# nonregulation-level-shifter-mk-2_1.net
KiCad netlist of a schematic drawn in EAGLE
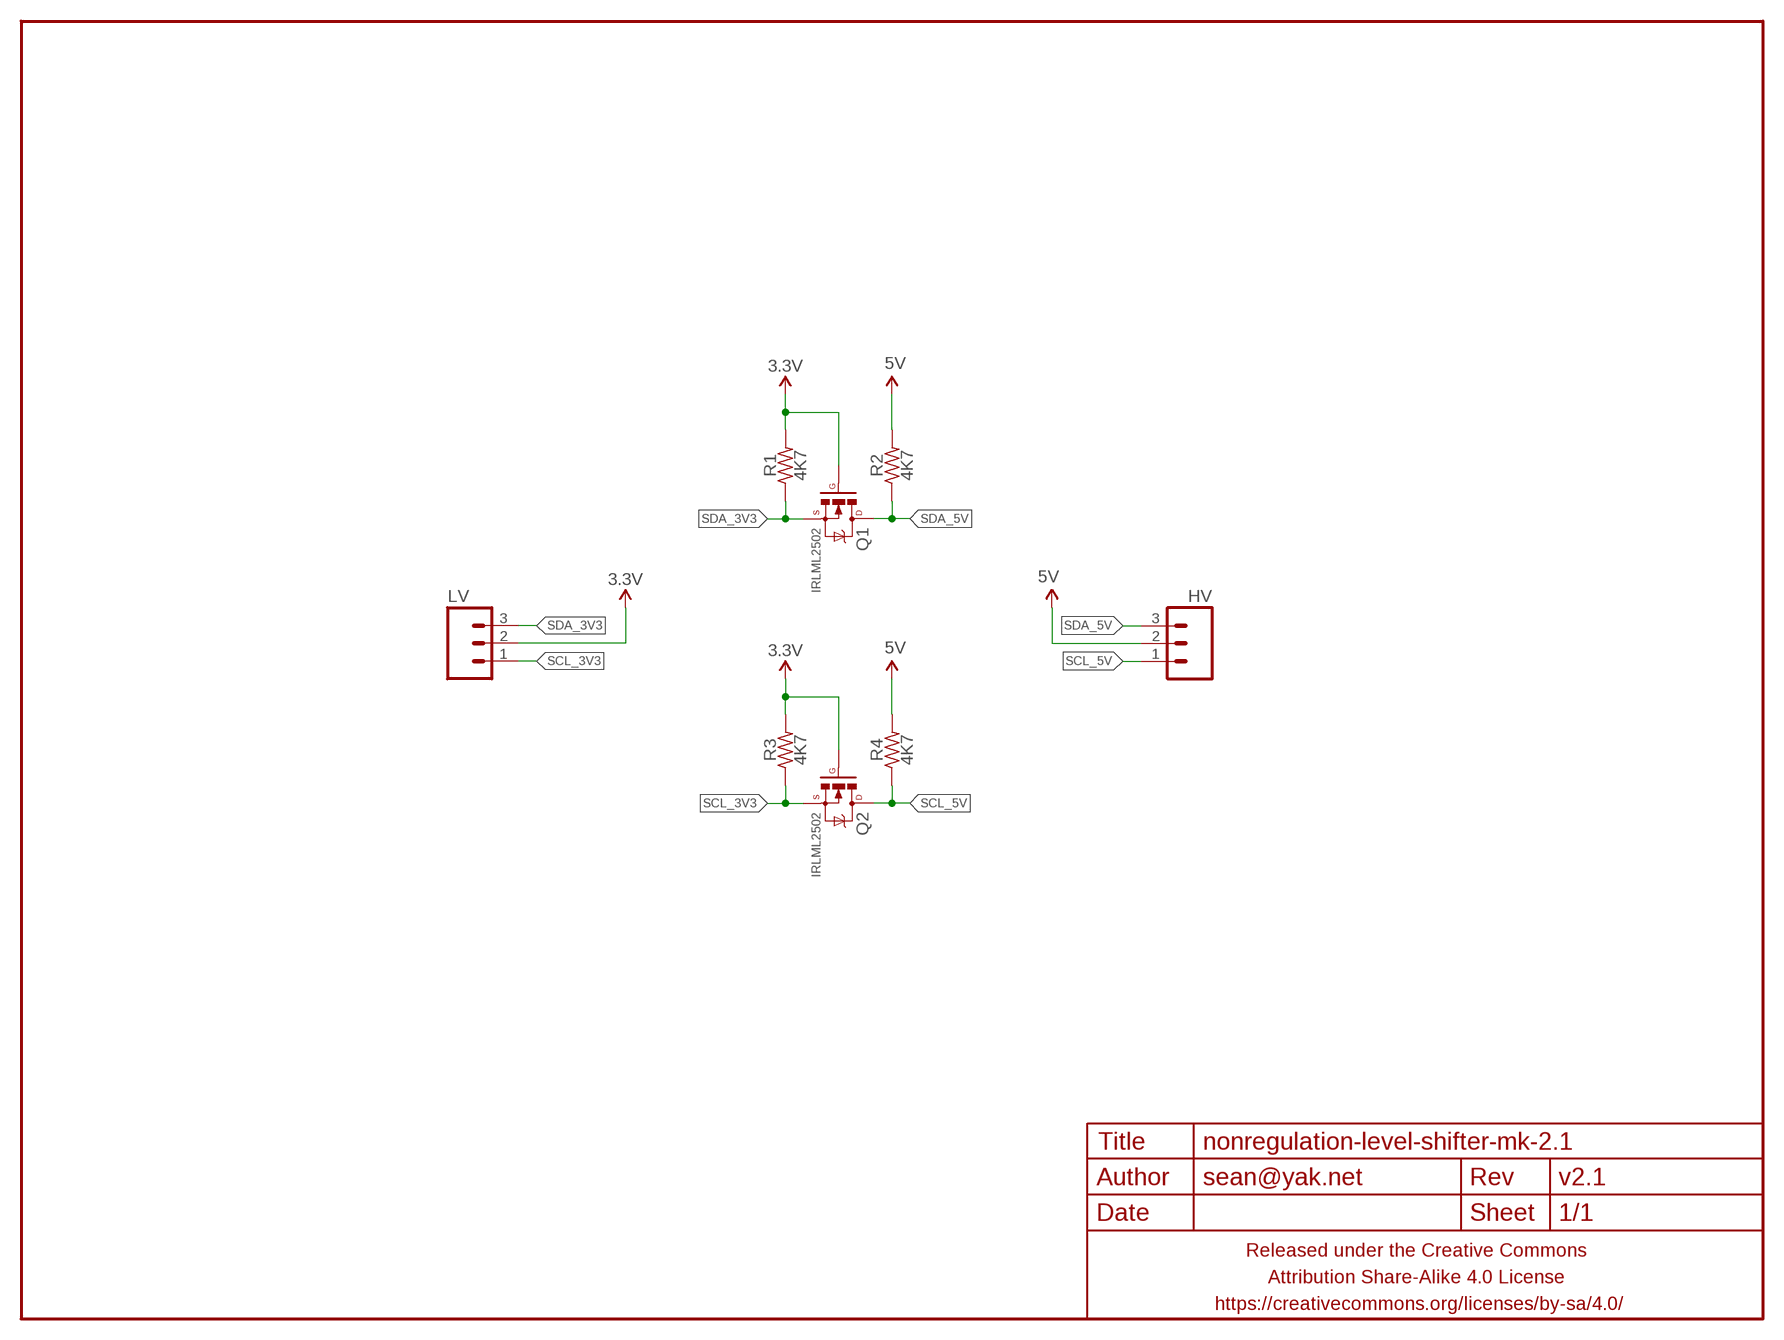
[diagram p0: schematic, sheet 1]

(export (version "E")
  (design (tool "Eeschema 10.0.6"))
  (components
    (comp (ref "FRAME1")
      (value "FRAME-LETTERNO_PACKAGE")
      (footprint "eagle-import:DUMMY")
      (fields (field (name "DESIGNER") "sean@yak.net") (field (name "VERSION") "v2.1"))
      (libsource (lib "eagle-import") (part "FRAME-LETTERNO_PACKAGE"))
    )
    (comp (ref "HV")
      (value "M03PTH-CENTERED")
      (footprint "eagle-import:1X03-CENTERED")
      (libsource (lib "eagle-import") (part "M03PTH-CENTERED"))
    )
    (comp (ref "LV")
      (value "M03PTH-CENTERED")
      (footprint "eagle-import:1X03-CENTERED")
      (libsource (lib "eagle-import") (part "M03PTH-CENTERED"))
    )
    (comp (ref "Q1")
      (value "IRLML2502")
      (footprint "eagle-import:SOT23")
      (libsource (lib "eagle-import") (part "MOSFET-NCHANNELIRLML2502"))
    )
    (comp (ref "Q2")
      (value "IRLML2502")
      (footprint "eagle-import:SOT23")
      (libsource (lib "eagle-import") (part "MOSFET-NCHANNELIRLML2502"))
    )
    (comp (ref "R1")
      (value "4K7")
      (footprint "eagle-import:R0603")
      (libsource (lib "eagle-import") (part "RESISTORR0603"))
    )
    (comp (ref "R2")
      (value "4K7")
      (footprint "eagle-import:R0603")
      (libsource (lib "eagle-import") (part "RESISTORR0603"))
    )
    (comp (ref "R3")
      (value "4K7")
      (footprint "eagle-import:R0603")
      (libsource (lib "eagle-import") (part "RESISTORR0603"))
    )
    (comp (ref "R4")
      (value "4K7")
      (footprint "eagle-import:R0603")
      (libsource (lib "eagle-import") (part "RESISTORR0603"))
    )
  )
  (nets
    (net (code "1") (name "3.3V") (class "Default")
      (node (ref "LV") (pin "2") (pinfunction "2_2") (pintype "passive"))
      (node (ref "Q1") (pin "1") (pinfunction "G_1") (pintype "passive"))
      (node (ref "Q2") (pin "1") (pinfunction "G_1") (pintype "passive"))
      (node (ref "R1") (pin "2") (pinfunction "2_2") (pintype "passive"))
      (node (ref "R3") (pin "2") (pinfunction "2_2") (pintype "passive"))
    )
    (net (code "2") (name "5V") (class "Default")
      (node (ref "HV") (pin "2") (pinfunction "2_2") (pintype "passive"))
      (node (ref "R2") (pin "2") (pinfunction "2_2") (pintype "passive"))
      (node (ref "R4") (pin "2") (pinfunction "2_2") (pintype "passive"))
    )
    (net (code "3") (name "SCL_3V3") (class "Default")
      (node (ref "LV") (pin "1") (pinfunction "1_1") (pintype "passive"))
      (node (ref "Q2") (pin "2") (pinfunction "S_2") (pintype "passive"))
      (node (ref "R3") (pin "1") (pinfunction "1_1") (pintype "passive"))
    )
    (net (code "4") (name "SCL_5V") (class "Default")
      (node (ref "HV") (pin "1") (pinfunction "1_1") (pintype "passive"))
      (node (ref "Q2") (pin "3") (pinfunction "D_3") (pintype "passive"))
      (node (ref "R4") (pin "1") (pinfunction "1_1") (pintype "passive"))
    )
    (net (code "5") (name "SDA_3V3") (class "Default")
      (node (ref "LV") (pin "3") (pinfunction "3_3") (pintype "passive"))
      (node (ref "Q1") (pin "2") (pinfunction "S_2") (pintype "passive"))
      (node (ref "R1") (pin "1") (pinfunction "1_1") (pintype "passive"))
    )
    (net (code "6") (name "SDA_5V") (class "Default")
      (node (ref "HV") (pin "3") (pinfunction "3_3") (pintype "passive"))
      (node (ref "Q1") (pin "3") (pinfunction "D_3") (pintype "passive"))
      (node (ref "R2") (pin "1") (pinfunction "1_1") (pintype "passive"))
    )
  )
)
